# AtmoOrb.net
KiCad netlist of a schematic drawn in EAGLE
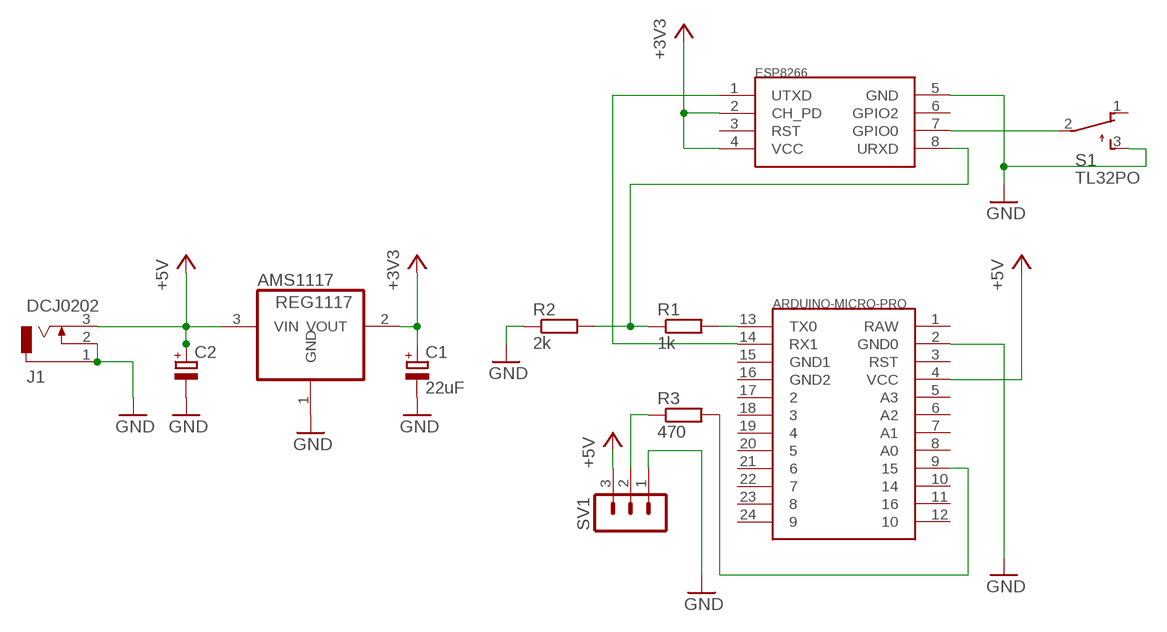
[diagram p0: schematic, sheet 1]

(export (version "E")
  (design (tool "Eeschema 10.0.6"))
  (components
    (comp (ref "AMS1117")
      (value "REG1117")
      (footprint "eagle-import:SOT223")
      (libsource (lib "eagle-import") (part "REG1117"))
    )
    (comp (ref "ARDUINO-MICRO-PRO")
      (value "ARDUINO_MICRO_PRO")
      (footprint "eagle-import:ARDUINO_MICRO_PRO")
      (libsource (lib "eagle-import") (part "ARDUINO_MICRO_PRO"))
    )
    (comp (ref "C1")
      (value "22uF")
      (footprint "eagle-import:TAP5-60")
      (libsource (lib "eagle-import") (part "CPOL-EUTAP5-60"))
    )
    (comp (ref "C2")
      (value "CPOL-EUTAP5-60")
      (footprint "eagle-import:TAP5-60")
      (libsource (lib "eagle-import") (part "CPOL-EUTAP5-60"))
    )
    (comp (ref "ESP8266")
      (value "ESP8266")
      (footprint "eagle-import:ESP8266")
      (libsource (lib "eagle-import") (part "ESP8266"))
    )
    (comp (ref "J1")
      (value "DCJ0202")
      (footprint "eagle-import:DCJ0202")
      (libsource (lib "eagle-import") (part "DCJ0202"))
    )
    (comp (ref "R1")
      (value "1k")
      (footprint "eagle-import:0207_10")
      (libsource (lib "eagle-import") (part "R-EU_0207/10"))
    )
    (comp (ref "R2")
      (value "2k")
      (footprint "eagle-import:0207_10")
      (libsource (lib "eagle-import") (part "R-EU_0207/10"))
    )
    (comp (ref "R3")
      (value "470")
      (footprint "eagle-import:0207_10")
      (libsource (lib "eagle-import") (part "R-EU_0207/10"))
    )
    (comp (ref "S1")
      (value "TL32PO")
      (footprint "eagle-import:TL3XPO")
      (libsource (lib "eagle-import") (part "TL32PO"))
    )
    (comp (ref "SV1")
      (value "MA03-1")
      (footprint "eagle-import:MA03-1")
      (libsource (lib "eagle-import") (part "MA03-1"))
    )
  )
  (nets
    (net (code "1") (name "+3V3") (class "Default")
      (node (ref "AMS1117") (pin "2") (pinfunction "VOUT_2") (pintype "output"))
      (node (ref "C1") (pin "+") (pinfunction "+_+") (pintype "passive"))
      (node (ref "ESP8266") (pin "2") (pinfunction "CH_PD_2") (pintype "bidirectional"))
      (node (ref "ESP8266") (pin "4") (pinfunction "VCC_4") (pintype "bidirectional"))
    )
    (net (code "2") (name "+5V") (class "Default")
      (node (ref "AMS1117") (pin "3") (pinfunction "VIN_3") (pintype "input"))
      (node (ref "ARDUINO-MICRO-PRO") (pin "4") (pinfunction "VCC_4") (pintype "bidirectional"))
      (node (ref "C2") (pin "+") (pinfunction "+_+") (pintype "passive"))
      (node (ref "J1") (pin "3") (pinfunction "3_3") (pintype "passive"))
      (node (ref "SV1") (pin "3") (pinfunction "3_3") (pintype "passive"))
    )
    (net (code "3") (name "GND") (class "Default")
      (node (ref "AMS1117") (pin "1") (pinfunction "GND_1") (pintype "power_in"))
      (node (ref "ARDUINO-MICRO-PRO") (pin "2") (pinfunction "GND0_2") (pintype "bidirectional"))
      (node (ref "C1") (pin "-") (pinfunction "-_-") (pintype "passive"))
      (node (ref "C2") (pin "-") (pinfunction "-_-") (pintype "passive"))
      (node (ref "ESP8266") (pin "5") (pinfunction "GND_5") (pintype "bidirectional"))
      (node (ref "J1") (pin "1") (pinfunction "1_1") (pintype "passive"))
      (node (ref "J1") (pin "2") (pinfunction "2_2") (pintype "passive"))
      (node (ref "R2") (pin "1") (pinfunction "1_1") (pintype "passive"))
      (node (ref "S1") (pin "3") (pinfunction "S_3") (pintype "passive"))
      (node (ref "SV1") (pin "1") (pinfunction "1_1") (pintype "passive"))
    )
    (net (code "4") (name "Net-(ARDUINO-MICRO-PRO-15)") (class "Default")
      (node (ref "ARDUINO-MICRO-PRO") (pin "9") (pinfunction "15_9") (pintype "bidirectional"))
      (node (ref "R3") (pin "2") (pinfunction "2_2") (pintype "passive"))
    )
    (net (code "5") (name "Net-(ARDUINO-MICRO-PRO-RX1)") (class "Default")
      (node (ref "ARDUINO-MICRO-PRO") (pin "14") (pinfunction "RX1_14") (pintype "bidirectional"))
      (node (ref "ESP8266") (pin "1") (pinfunction "UTXD_1") (pintype "bidirectional"))
    )
    (net (code "6") (name "Net-(ARDUINO-MICRO-PRO-TX0)") (class "Default")
      (node (ref "ARDUINO-MICRO-PRO") (pin "13") (pinfunction "TX0_13") (pintype "bidirectional"))
      (node (ref "R1") (pin "2") (pinfunction "2_2") (pintype "passive"))
    )
    (net (code "7") (name "Net-(ESP8266-GPIO0)") (class "Default")
      (node (ref "ESP8266") (pin "7") (pinfunction "GPIO0_7") (pintype "bidirectional"))
      (node (ref "S1") (pin "2") (pinfunction "P_2") (pintype "passive"))
    )
    (net (code "8") (name "Net-(ESP8266-URXD)") (class "Default")
      (node (ref "ESP8266") (pin "8") (pinfunction "URXD_8") (pintype "bidirectional"))
      (node (ref "R1") (pin "1") (pinfunction "1_1") (pintype "passive"))
      (node (ref "R2") (pin "2") (pinfunction "2_2") (pintype "passive"))
    )
    (net (code "9") (name "Net-(R3-Pad1)") (class "Default")
      (node (ref "R3") (pin "1") (pinfunction "1_1") (pintype "passive"))
      (node (ref "SV1") (pin "2") (pinfunction "2_2") (pintype "passive"))
    )
    (net (code "10") (name "unconnected-(ARDUINO-MICRO-PRO-2-Pad17)") (class "Default")
      (node (ref "ARDUINO-MICRO-PRO") (pin "17") (pinfunction "2_17") (pintype "bidirectional"))
    )
    (net (code "11") (name "unconnected-(ARDUINO-MICRO-PRO-3-Pad18)") (class "Default")
      (node (ref "ARDUINO-MICRO-PRO") (pin "18") (pinfunction "3_18") (pintype "bidirectional"))
    )
    (net (code "12") (name "unconnected-(ARDUINO-MICRO-PRO-4-Pad19)") (class "Default")
      (node (ref "ARDUINO-MICRO-PRO") (pin "19") (pinfunction "4_19") (pintype "bidirectional"))
    )
    (net (code "13") (name "unconnected-(ARDUINO-MICRO-PRO-5-Pad20)") (class "Default")
      (node (ref "ARDUINO-MICRO-PRO") (pin "20") (pinfunction "5_20") (pintype "bidirectional"))
    )
    (net (code "14") (name "unconnected-(ARDUINO-MICRO-PRO-6-Pad21)") (class "Default")
      (node (ref "ARDUINO-MICRO-PRO") (pin "21") (pinfunction "6_21") (pintype "bidirectional"))
    )
    (net (code "15") (name "unconnected-(ARDUINO-MICRO-PRO-7-Pad22)") (class "Default")
      (node (ref "ARDUINO-MICRO-PRO") (pin "22") (pinfunction "7_22") (pintype "bidirectional"))
    )
    (net (code "16") (name "unconnected-(ARDUINO-MICRO-PRO-8-Pad23)") (class "Default")
      (node (ref "ARDUINO-MICRO-PRO") (pin "23") (pinfunction "8_23") (pintype "bidirectional"))
    )
    (net (code "17") (name "unconnected-(ARDUINO-MICRO-PRO-9-Pad24)") (class "Default")
      (node (ref "ARDUINO-MICRO-PRO") (pin "24") (pinfunction "9_24") (pintype "bidirectional"))
    )
    (net (code "18") (name "unconnected-(ARDUINO-MICRO-PRO-10-Pad12)") (class "Default")
      (node (ref "ARDUINO-MICRO-PRO") (pin "12") (pinfunction "10_12") (pintype "bidirectional"))
    )
    (net (code "19") (name "unconnected-(ARDUINO-MICRO-PRO-14-Pad10)") (class "Default")
      (node (ref "ARDUINO-MICRO-PRO") (pin "10") (pinfunction "14_10") (pintype "bidirectional"))
    )
    (net (code "20") (name "unconnected-(ARDUINO-MICRO-PRO-16-Pad11)") (class "Default")
      (node (ref "ARDUINO-MICRO-PRO") (pin "11") (pinfunction "16_11") (pintype "bidirectional"))
    )
    (net (code "21") (name "unconnected-(ARDUINO-MICRO-PRO-A0-Pad8)") (class "Default")
      (node (ref "ARDUINO-MICRO-PRO") (pin "8") (pinfunction "A0_8") (pintype "bidirectional"))
    )
    (net (code "22") (name "unconnected-(ARDUINO-MICRO-PRO-A1-Pad7)") (class "Default")
      (node (ref "ARDUINO-MICRO-PRO") (pin "7") (pinfunction "A1_7") (pintype "bidirectional"))
    )
    (net (code "23") (name "unconnected-(ARDUINO-MICRO-PRO-A2-Pad6)") (class "Default")
      (node (ref "ARDUINO-MICRO-PRO") (pin "6") (pinfunction "A2_6") (pintype "bidirectional"))
    )
    (net (code "24") (name "unconnected-(ARDUINO-MICRO-PRO-A3-Pad5)") (class "Default")
      (node (ref "ARDUINO-MICRO-PRO") (pin "5") (pinfunction "A3_5") (pintype "bidirectional"))
    )
    (net (code "25") (name "unconnected-(ARDUINO-MICRO-PRO-GND1-Pad15)") (class "Default")
      (node (ref "ARDUINO-MICRO-PRO") (pin "15") (pinfunction "GND1_15") (pintype "bidirectional"))
    )
    (net (code "26") (name "unconnected-(ARDUINO-MICRO-PRO-GND2-Pad16)") (class "Default")
      (node (ref "ARDUINO-MICRO-PRO") (pin "16") (pinfunction "GND2_16") (pintype "bidirectional"))
    )
    (net (code "27") (name "unconnected-(ARDUINO-MICRO-PRO-RAW-Pad1)") (class "Default")
      (node (ref "ARDUINO-MICRO-PRO") (pin "1") (pinfunction "RAW_1") (pintype "bidirectional"))
    )
    (net (code "28") (name "unconnected-(ARDUINO-MICRO-PRO-RST-Pad3)") (class "Default")
      (node (ref "ARDUINO-MICRO-PRO") (pin "3") (pinfunction "RST_3") (pintype "bidirectional"))
    )
    (net (code "29") (name "unconnected-(ESP8266-GPIO2-Pad6)") (class "Default")
      (node (ref "ESP8266") (pin "6") (pinfunction "GPIO2_6") (pintype "bidirectional"))
    )
    (net (code "30") (name "unconnected-(ESP8266-RST-Pad3)") (class "Default")
      (node (ref "ESP8266") (pin "3") (pinfunction "RST_3") (pintype "bidirectional"))
    )
    (net (code "31") (name "unconnected-(S1-O-Pad1)") (class "Default")
      (node (ref "S1") (pin "1") (pinfunction "O_1") (pintype "passive"))
    )
  )
)
